# DC_Motorsteuerung_Piggyboard.net
KiCad netlist of a schematic drawn in EAGLE
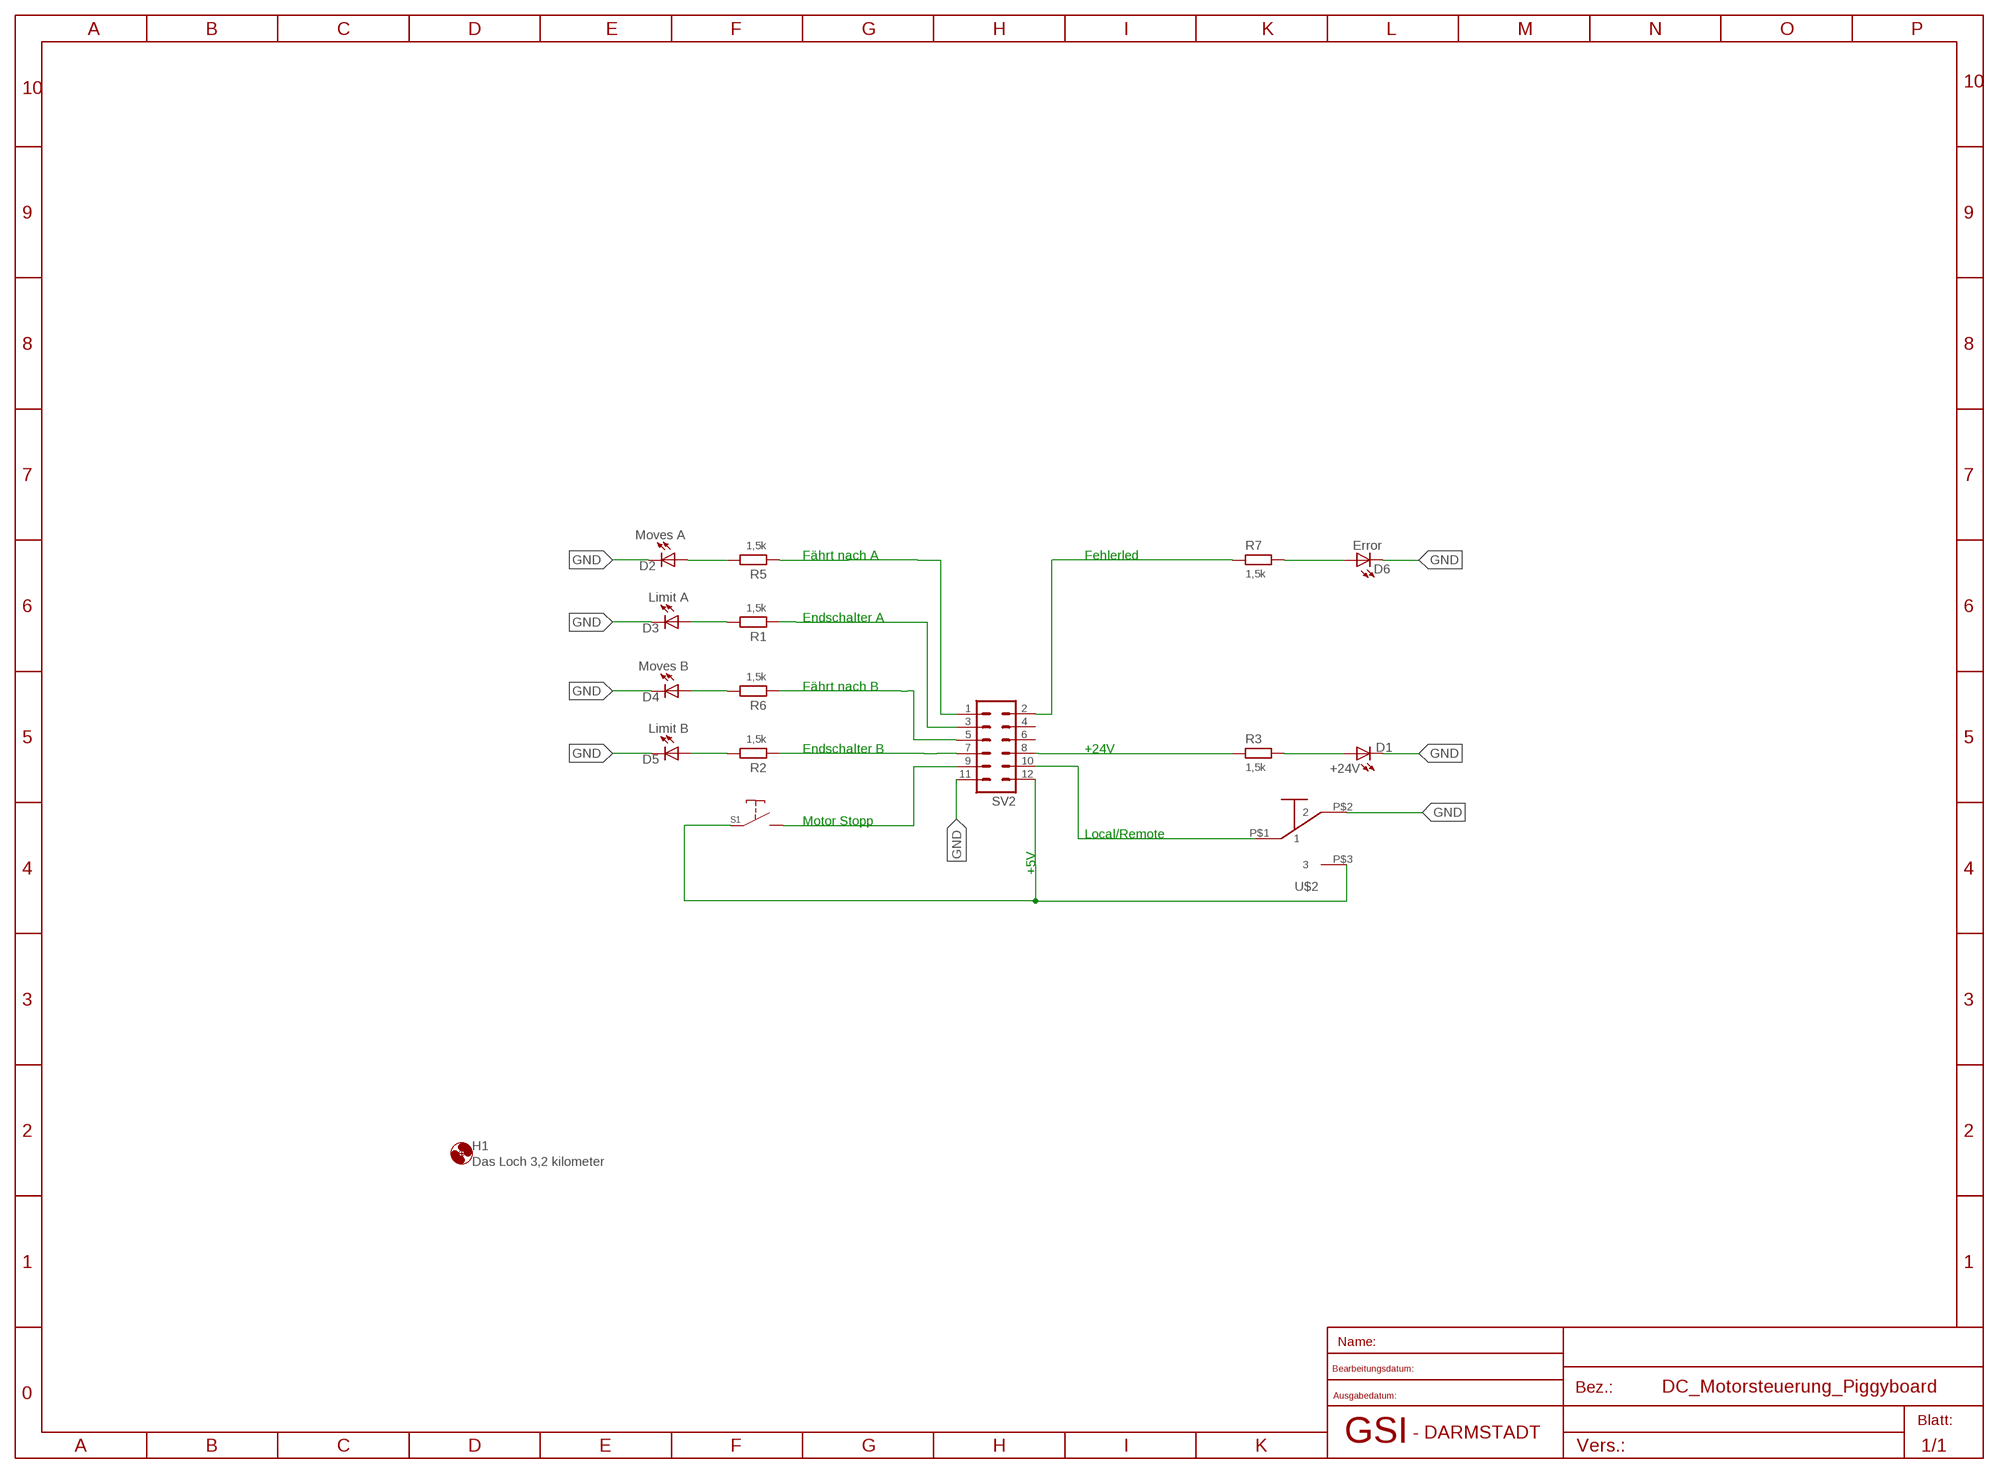
[diagram p0: schematic, sheet 1]

(export (version "E")
  (design (tool "Eeschema 10.0.6"))
  (components
    (comp (ref "D1")
      (value "+24V")
      (footprint "eagle-import:LED3MMCASE")
      (libsource (lib "eagle-import") (part "LED3MM"))
    )
    (comp (ref "D2")
      (value "Moves A")
      (footprint "eagle-import:LED3MMCASE")
      (libsource (lib "eagle-import") (part "LED3MM"))
    )
    (comp (ref "D3")
      (value "Limit A")
      (footprint "eagle-import:LED3MMCASE")
      (libsource (lib "eagle-import") (part "LED3MM"))
    )
    (comp (ref "D4")
      (value "Moves B")
      (footprint "eagle-import:LED3MMCASE")
      (libsource (lib "eagle-import") (part "LED3MM"))
    )
    (comp (ref "D5")
      (value "Limit B")
      (footprint "eagle-import:LED3MMCASE")
      (libsource (lib "eagle-import") (part "LED3MM"))
    )
    (comp (ref "D6")
      (value "Error")
      (footprint "eagle-import:LED3MMCASE")
      (libsource (lib "eagle-import") (part "LED3MM"))
    )
    (comp (ref "H1")
      (value "Das Loch 3,2 kilometer")
      (footprint "eagle-import:3,2")
      (libsource (lib "eagle-import") (part "MOUNT-HOLE3.2"))
    )
    (comp (ref "R1")
      (value "1,5k")
      (footprint "eagle-import:R_0,4W")
      (libsource (lib "eagle-import") (part "R_0,4W"))
    )
    (comp (ref "R2")
      (value "1,5k")
      (footprint "eagle-import:R_0,4W")
      (libsource (lib "eagle-import") (part "R_0,4W"))
    )
    (comp (ref "R3")
      (value "1,5k")
      (footprint "eagle-import:R_0,4W")
      (libsource (lib "eagle-import") (part "R_0,4W"))
    )
    (comp (ref "R5")
      (value "1,5k")
      (footprint "eagle-import:R_0,4W")
      (libsource (lib "eagle-import") (part "R_0,4W"))
    )
    (comp (ref "R6")
      (value "1,5k")
      (footprint "eagle-import:R_0,4W")
      (libsource (lib "eagle-import") (part "R_0,4W"))
    )
    (comp (ref "R7")
      (value "1,5k")
      (footprint "eagle-import:R_0,4W")
      (libsource (lib "eagle-import") (part "R_0,4W"))
    )
    (comp (ref "S1")
      (value "MotorStopp")
      (footprint "eagle-import:1_POL_ABGW")
      (libsource (lib "eagle-import") (part "DRUCKTASTER_ABGW"))
    )
    (comp (ref "SV2")
      (value "MA06-2")
      (footprint "eagle-import:MA06-2")
      (libsource (lib "eagle-import") (part "MA06-2"))
    )
    (comp (ref "U$2")
      (value "UMSCHALTER_SINGLE_POLE")
      (footprint "eagle-import:UMSCHALTER_SINGLE_POLE")
      (libsource (lib "eagle-import") (part "UMSCHALTER_SINGLE_POLE"))
    )
  )
  (nets
    (net (code "1") (name "GND") (class "Default")
      (node (ref "D1") (pin "P$2") (pinfunction "C_P$2") (pintype "passive"))
      (node (ref "D2") (pin "P$2") (pinfunction "C_P$2") (pintype "passive"))
      (node (ref "D3") (pin "P$2") (pinfunction "C_P$2") (pintype "passive"))
      (node (ref "D4") (pin "P$2") (pinfunction "C_P$2") (pintype "passive"))
      (node (ref "D5") (pin "P$2") (pinfunction "C_P$2") (pintype "passive"))
      (node (ref "D6") (pin "P$2") (pinfunction "C_P$2") (pintype "passive"))
      (node (ref "SV2") (pin "11") (pinfunction "11_11") (pintype "passive"))
      (node (ref "U$2") (pin "P$2") (pinfunction "2_P$2") (pintype "passive"))
    )
    (net (code "2") (name "Net-(D1-A)") (class "Default")
      (node (ref "D1") (pin "P$1") (pinfunction "A_P$1") (pintype "passive"))
      (node (ref "R3") (pin "2") (pinfunction "2_2") (pintype "passive"))
    )
    (net (code "3") (name "Net-(D2-A)") (class "Default")
      (node (ref "D2") (pin "P$1") (pinfunction "A_P$1") (pintype "passive"))
      (node (ref "R5") (pin "2") (pinfunction "2_2") (pintype "passive"))
    )
    (net (code "4") (name "Net-(D3-A)") (class "Default")
      (node (ref "D3") (pin "P$1") (pinfunction "A_P$1") (pintype "passive"))
      (node (ref "R1") (pin "2") (pinfunction "2_2") (pintype "passive"))
    )
    (net (code "5") (name "Net-(D4-A)") (class "Default")
      (node (ref "D4") (pin "P$1") (pinfunction "A_P$1") (pintype "passive"))
      (node (ref "R6") (pin "2") (pinfunction "2_2") (pintype "passive"))
    )
    (net (code "6") (name "Net-(D5-A)") (class "Default")
      (node (ref "D5") (pin "P$1") (pinfunction "A_P$1") (pintype "passive"))
      (node (ref "R2") (pin "2") (pinfunction "2_2") (pintype "passive"))
    )
    (net (code "7") (name "Net-(D6-A)") (class "Default")
      (node (ref "D6") (pin "P$1") (pinfunction "A_P$1") (pintype "passive"))
      (node (ref "R7") (pin "2") (pinfunction "2_2") (pintype "passive"))
    )
    (net (code "8") (name "Net-(R1-Pad1)") (class "Default")
      (node (ref "R1") (pin "1") (pinfunction "1_1") (pintype "passive"))
      (node (ref "SV2") (pin "3") (pinfunction "3_3") (pintype "passive"))
    )
    (net (code "9") (name "Net-(R2-Pad1)") (class "Default")
      (node (ref "R2") (pin "1") (pinfunction "1_1") (pintype "passive"))
      (node (ref "SV2") (pin "7") (pinfunction "7_7") (pintype "passive"))
    )
    (net (code "10") (name "Net-(R3-Pad1)") (class "Default")
      (node (ref "R3") (pin "1") (pinfunction "1_1") (pintype "passive"))
      (node (ref "SV2") (pin "8") (pinfunction "8_8") (pintype "passive"))
    )
    (net (code "11") (name "Net-(R5-Pad1)") (class "Default")
      (node (ref "R5") (pin "1") (pinfunction "1_1") (pintype "passive"))
      (node (ref "SV2") (pin "1") (pinfunction "1_1") (pintype "passive"))
    )
    (net (code "12") (name "Net-(R6-Pad1)") (class "Default")
      (node (ref "R6") (pin "1") (pinfunction "1_1") (pintype "passive"))
      (node (ref "SV2") (pin "5") (pinfunction "5_5") (pintype "passive"))
    )
    (net (code "13") (name "Net-(R7-Pad1)") (class "Default")
      (node (ref "R7") (pin "1") (pinfunction "1_1") (pintype "passive"))
      (node (ref "SV2") (pin "2") (pinfunction "2_2") (pintype "passive"))
    )
    (net (code "14") (name "Net-(S1-C)") (class "Default")
      (node (ref "S1") (pin "S1") (pinfunction "C_S1") (pintype "passive"))
      (node (ref "SV2") (pin "12") (pinfunction "12_12") (pintype "passive"))
      (node (ref "U$2") (pin "P$3") (pinfunction "3_P$3") (pintype "passive"))
    )
    (net (code "15") (name "Net-(S1-N0)") (class "Default")
      (node (ref "S1") (pin "S2") (pinfunction "N0_S2") (pintype "passive"))
      (node (ref "SV2") (pin "9") (pinfunction "9_9") (pintype "passive"))
    )
    (net (code "16") (name "Net-(U$2-1)") (class "Default")
      (node (ref "SV2") (pin "10") (pinfunction "10_10") (pintype "passive"))
      (node (ref "U$2") (pin "P$1") (pinfunction "1_P$1") (pintype "passive"))
    )
    (net (code "17") (name "unconnected-(SV2-Pad4)") (class "Default")
      (node (ref "SV2") (pin "4") (pinfunction "4_4") (pintype "passive"))
    )
    (net (code "18") (name "unconnected-(SV2-Pad6)") (class "Default")
      (node (ref "SV2") (pin "6") (pinfunction "6_6") (pintype "passive"))
    )
  )
)
